# 09_CAN.net
KiCad netlist of a schematic drawn in Altium Designer
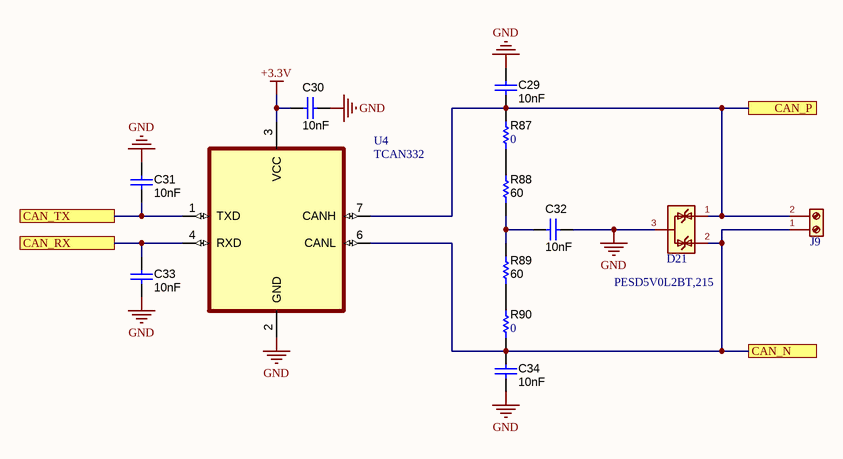
[diagram p0: 09_CAN.SchDoc]

(export (version "E")
  (design (tool "Eeschema 10.0.6"))
  (components
    (comp (ref "C29")
      (value "CAP 10nF 0603")
      (footprint "0603")
      (description "CAP, CERM, 10 nF, 50 V, +/- 10%, X7R, AEC-Q200 Grade 1, 0603")
      (fields
        (field (name "MANUFACTURER") "MuRata")
        (field (name "PARTNUMBER") "GCM188R70J225KE22D")
        (field (name "VALUEDISPLAYED") "10nF")
        (field (name "PUBLISHER") "Texas Instruments")
      )
      (libsource (lib "PROC051C_AWR1843BOOST_RevC") (part "CAP 10nF 0603"))
    )
    (comp (ref "C30")
      (value "CAP 10nF 0603")
      (footprint "0603")
      (description "CAP, CERM, 10 nF, 50 V, +/- 10%, X7R, AEC-Q200 Grade 1, 0603")
      (fields
        (field (name "MANUFACTURER") "MuRata")
        (field (name "PARTNUMBER") "GCM188R70J225KE22D")
        (field (name "VALUEDISPLAYED") "10nF")
        (field (name "PUBLISHER") "Texas Instruments")
      )
      (libsource (lib "PROC051C_AWR1843BOOST_RevC") (part "CAP 10nF 0603"))
    )
    (comp (ref "C31")
      (value "CAP 10nF 0603")
      (footprint "0603")
      (description "CAP, CERM, 10 nF, 50 V, +/- 10%, X7R, AEC-Q200 Grade 1, 0603")
      (fields
        (field (name "MANUFACTURER") "MuRata")
        (field (name "PARTNUMBER") "GCM188R70J225KE22D")
        (field (name "VALUEDISPLAYED") "10nF")
        (field (name "PUBLISHER") "Texas Instruments")
      )
      (libsource (lib "PROC051C_AWR1843BOOST_RevC") (part "CAP 10nF 0603"))
    )
    (comp (ref "C32")
      (value "CAP 10nF 0603")
      (footprint "0603")
      (description "CAP, CERM, 10 nF, 50 V, +/- 10%, X7R, AEC-Q200 Grade 1, 0603")
      (fields
        (field (name "MANUFACTURER") "MuRata")
        (field (name "PARTNUMBER") "GCM188R70J225KE22D")
        (field (name "VALUEDISPLAYED") "10nF")
        (field (name "PUBLISHER") "Texas Instruments")
      )
      (libsource (lib "PROC051C_AWR1843BOOST_RevC") (part "CAP 10nF 0603"))
    )
    (comp (ref "C33")
      (value "CAP 10nF 0603")
      (footprint "0603")
      (description "CAP, CERM, 10 nF, 50 V, +/- 10%, X7R, AEC-Q200 Grade 1, 0603")
      (fields
        (field (name "MANUFACTURER") "MuRata")
        (field (name "PARTNUMBER") "GCM188R70J225KE22D")
        (field (name "VALUEDISPLAYED") "10nF")
        (field (name "PUBLISHER") "Texas Instruments")
      )
      (libsource (lib "PROC051C_AWR1843BOOST_RevC") (part "CAP 10nF 0603"))
    )
    (comp (ref "C34")
      (value "CAP 10nF 0603")
      (footprint "0603")
      (description "CAP, CERM, 10 nF, 50 V, +/- 10%, X7R, AEC-Q200 Grade 1, 0603")
      (fields
        (field (name "MANUFACTURER") "MuRata")
        (field (name "PARTNUMBER") "GCM188R70J225KE22D")
        (field (name "VALUEDISPLAYED") "10nF")
        (field (name "PUBLISHER") "Texas Instruments")
      )
      (libsource (lib "PROC051C_AWR1843BOOST_RevC") (part "CAP 10nF 0603"))
    )
    (comp (ref "D21")
      (value "PESD5V0L2BT,215")
      (footprint "SOT-23")
      (libsource (lib "PROC051C_AWR1843BOOST_RevC") (part "PESD5V0L2BT,215"))
    )
    (comp (ref "J9")
      (value "Terminal_01x02_P5.00")
      (footprint "TerminalBlock_Phoenix_PT-1,5-2-5.0-H_1x02_P5.00mm_Horizontal")
      (libsource (lib "PROC051C_AWR1843BOOST_RevC") (part "Terminal_01x02_P5.00"))
    )
    (comp (ref "R87")
      (value "ERJ-2GE0R00X")
      (footprint "0402L")
      (description "RES, 0, 5%, 0.1 W, AEC-Q200 Grade 0, 0402")
      (fields (field (name "MANUFACTURER") "Panasonic") (field (name "VALUEDISPLAYED") "0"))
      (libsource (lib "PROC051C_AWR1843BOOST_RevC") (part "RES 0R 0402 0.1W"))
    )
    (comp (ref "R88")
      (value "MCT06030Z0000ZP500")
      (footprint "0603")
      (description "RES, 60, 5%, 0.125 W, 0603")
      (fields
        (field (name "MANUFACTURER") "Vishay/Beyschlag")
        (field (name "VALUEDISPLAYED") "60")
        (field (name "PUBLISHER") "Texas Instruments")
      )
      (libsource (lib "PROC051C_AWR1843BOOST_RevC") (part "RES 60R 0603"))
    )
    (comp (ref "R89")
      (value "MCT06030Z0000ZP500")
      (footprint "0603")
      (description "RES, 60, 5%, 0.125 W, 0603")
      (fields
        (field (name "MANUFACTURER") "Vishay/Beyschlag")
        (field (name "VALUEDISPLAYED") "60")
        (field (name "PUBLISHER") "Texas Instruments")
      )
      (libsource (lib "PROC051C_AWR1843BOOST_RevC") (part "RES 60R 0603"))
    )
    (comp (ref "R90")
      (value "ERJ-2GE0R00X")
      (footprint "0402L")
      (description "RES, 0, 5%, 0.1 W, AEC-Q200 Grade 0, 0402")
      (fields (field (name "MANUFACTURER") "Panasonic") (field (name "VALUEDISPLAYED") "0"))
      (libsource (lib "PROC051C_AWR1843BOOST_RevC") (part "RES 0R 0402 0.1W"))
    )
    (comp (ref "U4")
      (value "TCAN332")
      (footprint "SOIC127P599X175-8N")
      (description "3.3-V CAN Transceivers")
      (fields (field (name "MF") "Texas Instruments") (field (name "MP") "TCAN332DR"))
      (libsource (lib "PROC051C_AWR1843BOOST_RevC") (part "TCAN332DR"))
    )
  )
  (nets
    (net (code "1") (name "+3.3V") (class "Default")
      (node (ref "C30") (pin "2") (pinfunction "2_2") (pintype "passive"))
      (node (ref "U4") (pin "3") (pinfunction "VCC_3") (pintype "power_in"))
    )
    (net (code "2") (name "/CAN_N") (class "Default")
      (node (ref "C34") (pin "1") (pinfunction "1_1") (pintype "passive"))
      (node (ref "D21") (pin "2") (pinfunction "K_2") (pintype "passive"))
      (node (ref "J9") (pin "1") (pinfunction "Pin_1_1") (pintype "passive"))
      (node (ref "R90") (pin "1") (pinfunction "1_1") (pintype "passive"))
      (node (ref "U4") (pin "6") (pinfunction "CANL_6") (pintype "bidirectional"))
    )
    (net (code "3") (name "/CAN_P") (class "Default")
      (node (ref "C29") (pin "2") (pinfunction "2_2") (pintype "passive"))
      (node (ref "D21") (pin "1") (pinfunction "K_1") (pintype "passive"))
      (node (ref "J9") (pin "2") (pinfunction "Pin_2_2") (pintype "passive"))
      (node (ref "R87") (pin "2") (pinfunction "2_2") (pintype "passive"))
      (node (ref "U4") (pin "7") (pinfunction "CANH_7") (pintype "bidirectional"))
    )
    (net (code "4") (name "/CAN_RX") (class "Default")
      (node (ref "C33") (pin "1") (pinfunction "1_1") (pintype "passive"))
      (node (ref "U4") (pin "4") (pinfunction "RXD_4") (pintype "bidirectional"))
    )
    (net (code "5") (name "/CAN_TX") (class "Default")
      (node (ref "C31") (pin "2") (pinfunction "2_2") (pintype "passive"))
      (node (ref "U4") (pin "1") (pinfunction "TXD_1") (pintype "bidirectional"))
    )
    (net (code "6") (name "GND") (class "Default")
      (node (ref "C29") (pin "1") (pinfunction "1_1") (pintype "passive"))
      (node (ref "C30") (pin "1") (pinfunction "1_1") (pintype "passive"))
      (node (ref "C31") (pin "1") (pinfunction "1_1") (pintype "passive"))
      (node (ref "C32") (pin "1") (pinfunction "1_1") (pintype "passive"))
      (node (ref "C33") (pin "2") (pinfunction "2_2") (pintype "passive"))
      (node (ref "C34") (pin "2") (pinfunction "2_2") (pintype "passive"))
      (node (ref "D21") (pin "3") (pinfunction "A_3") (pintype "passive"))
      (node (ref "U4") (pin "2") (pinfunction "GND_2") (pintype "power_in"))
    )
    (net (code "7") (name "Net-(C32-Pad2)") (class "Default")
      (node (ref "C32") (pin "2") (pinfunction "2_2") (pintype "passive"))
      (node (ref "R88") (pin "1") (pinfunction "1_1") (pintype "passive"))
      (node (ref "R89") (pin "2") (pinfunction "2_2") (pintype "passive"))
    )
    (net (code "8") (name "Net-(R87-Pad1)") (class "Default")
      (node (ref "R87") (pin "1") (pinfunction "1_1") (pintype "passive"))
      (node (ref "R88") (pin "2") (pinfunction "2_2") (pintype "passive"))
    )
    (net (code "9") (name "Net-(R89-Pad1)") (class "Default")
      (node (ref "R89") (pin "1") (pinfunction "1_1") (pintype "passive"))
      (node (ref "R90") (pin "2") (pinfunction "2_2") (pintype "passive"))
    )
  )
)
